# 12-Electrodes.net
KiCad netlist of a schematic drawn in Altium Designer
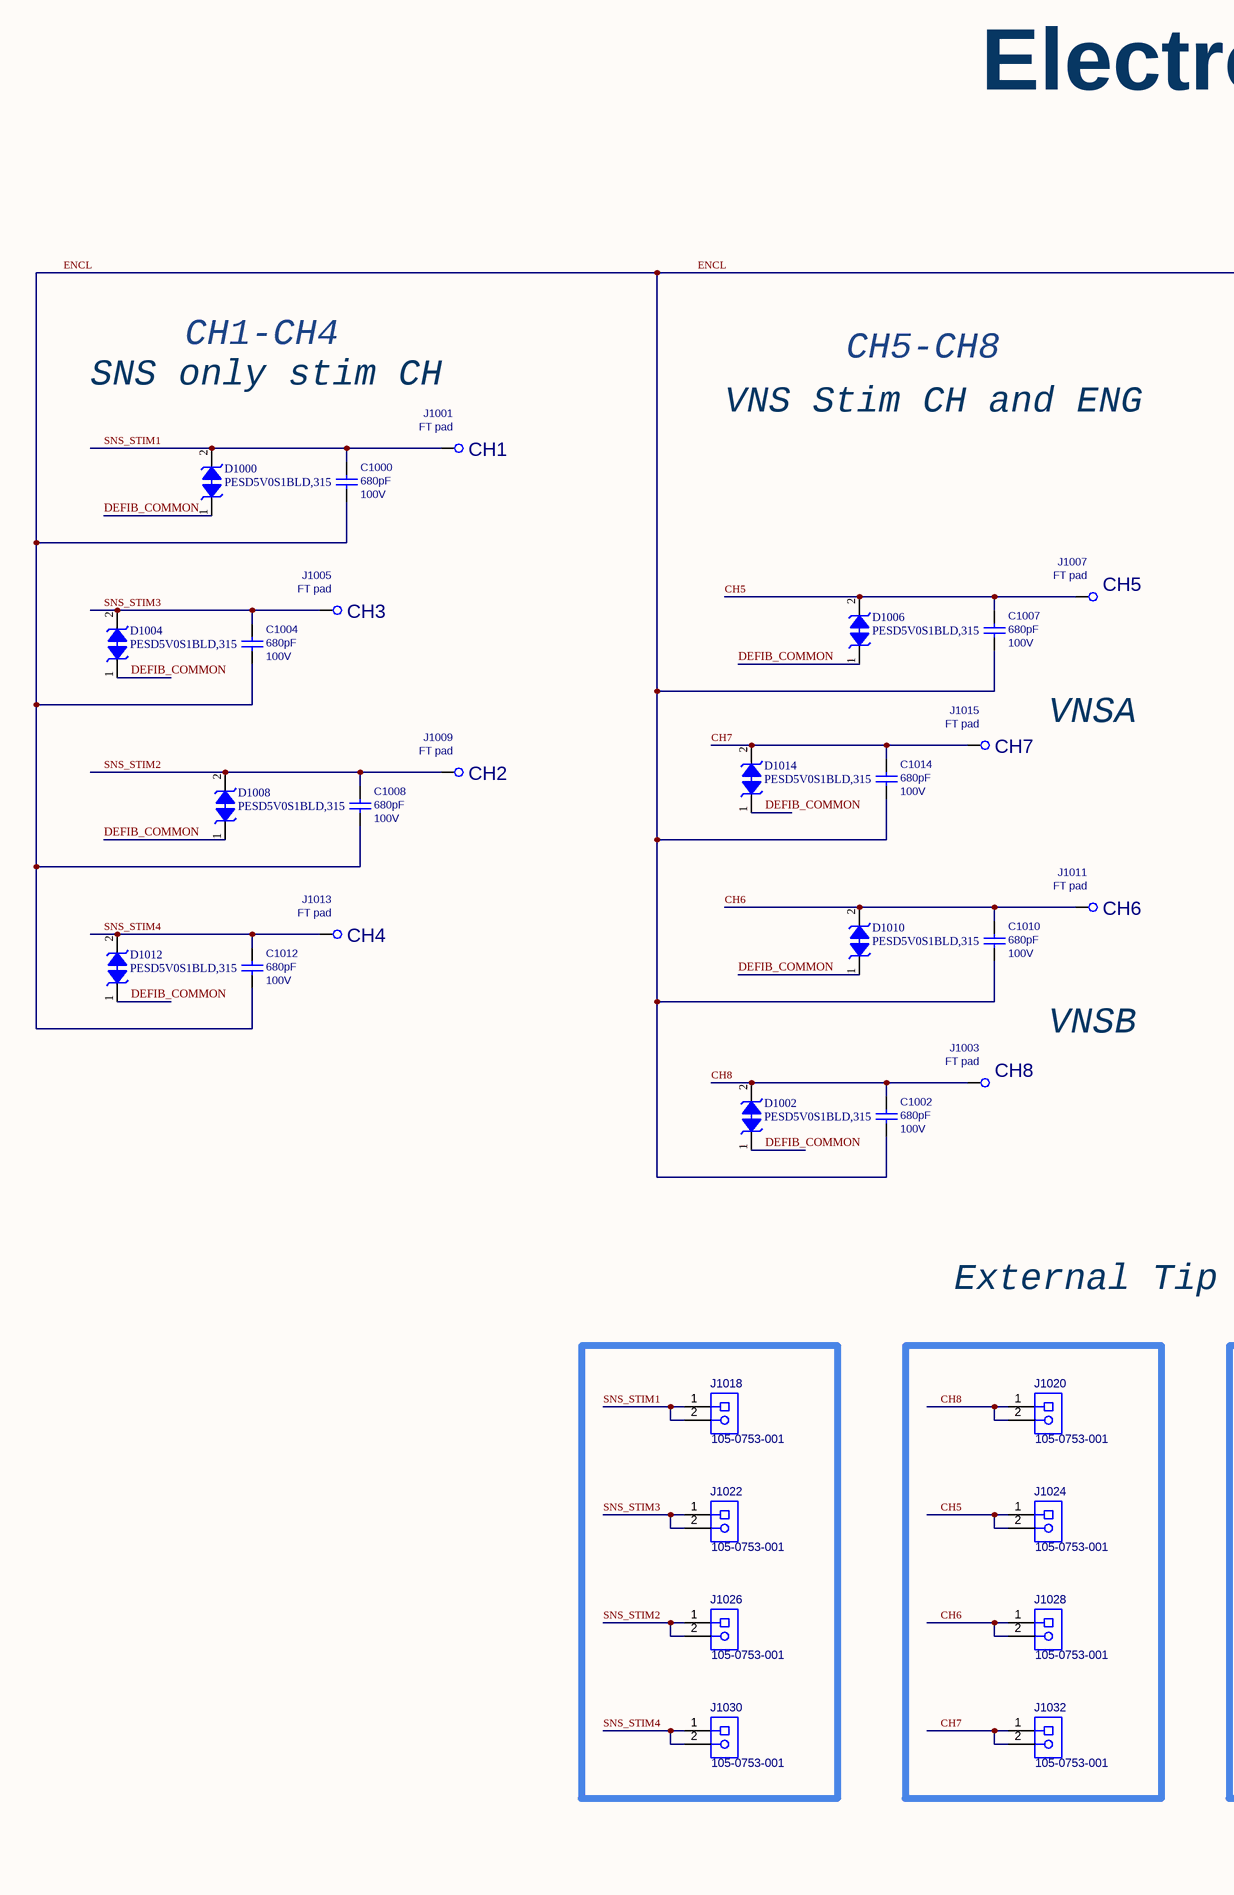
[diagram p0: 12-Electrodes.SchDoc, left]
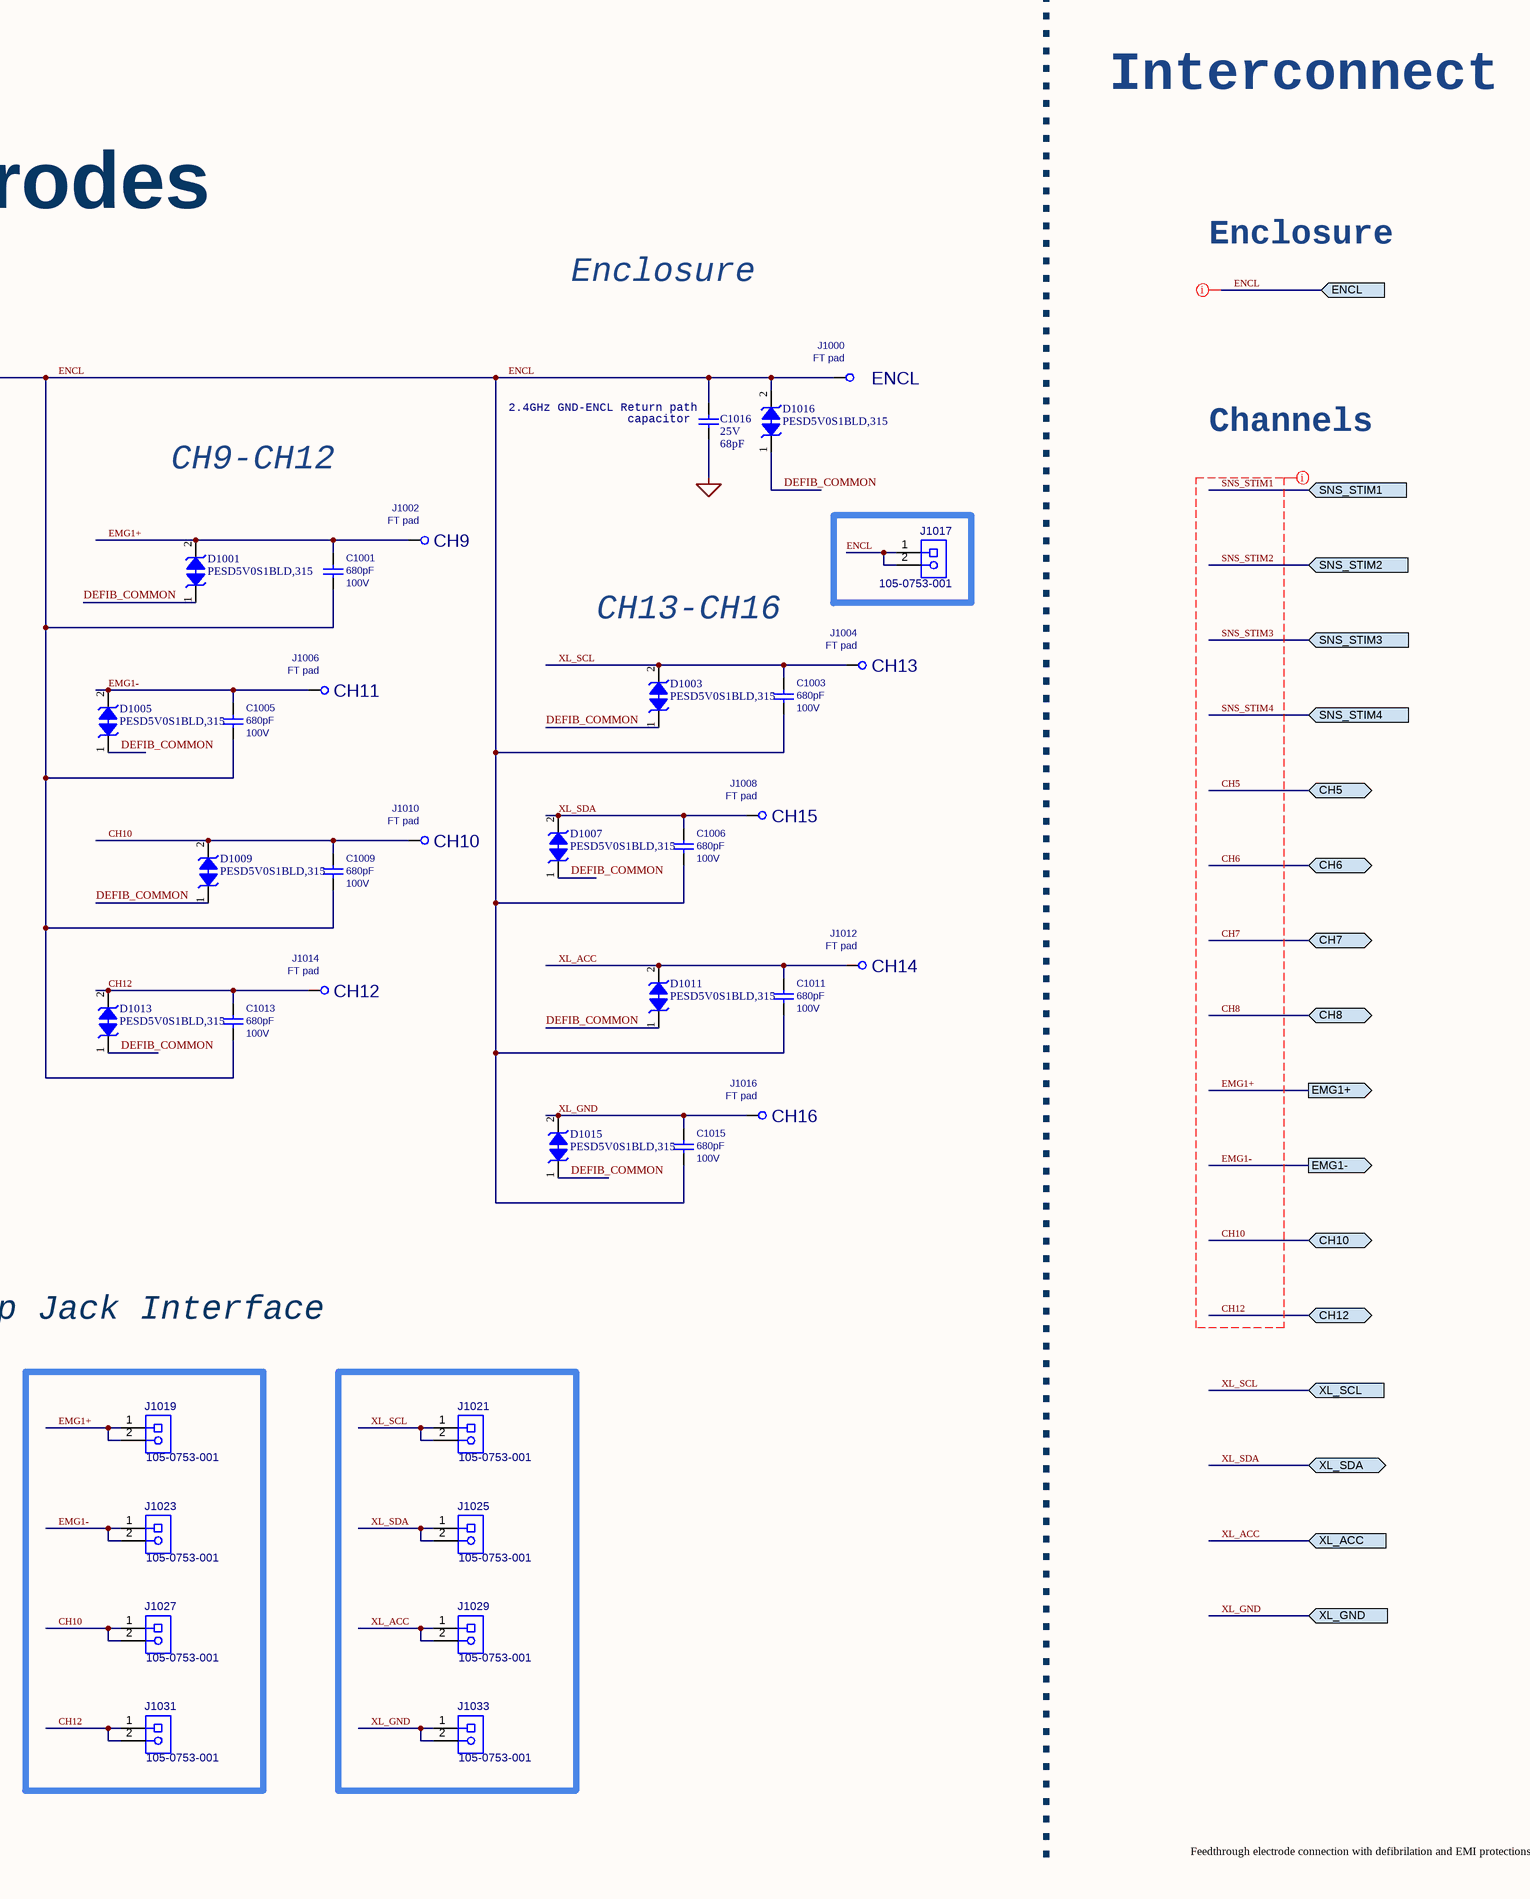
[diagram p1: 12-Electrodes.SchDoc, right]

(export (version "E")
  (design (tool "Eeschema 10.0.6"))
  (components
    (comp (ref "C1000")
      (value "680pF")
      (footprint "CAP0402_REDUCED")
      (description "Capacitor, 680pF, C0G, 100V, 5%, 0402")
      (fields
        (field (name "MANUFACTURER") "TDK")
        (field (name "RATING") "100V")
        (field (name "MANUFACTURER PART NUMBER") "C1005C0G2A681J050BE")
      )
      (libsource (lib "MP-LIBRARY") (part "C1005C0G2A681J050BE"))
    )
    (comp (ref "C1001")
      (value "680pF")
      (footprint "CAP0402_REDUCED")
      (description "Capacitor, 680pF, C0G, 100V, 5%, 0402")
      (fields
        (field (name "MANUFACTURER") "TDK")
        (field (name "RATING") "100V")
        (field (name "MANUFACTURER PART NUMBER") "C1005C0G2A681J050BE")
      )
      (libsource (lib "MP-LIBRARY") (part "C1005C0G2A681J050BE"))
    )
    (comp (ref "C1002")
      (value "680pF")
      (footprint "CAP0402_REDUCED")
      (description "Capacitor, 680pF, C0G, 100V, 5%, 0402")
      (fields
        (field (name "MANUFACTURER") "TDK")
        (field (name "RATING") "100V")
        (field (name "MANUFACTURER PART NUMBER") "C1005C0G2A681J050BE")
      )
      (libsource (lib "MP-LIBRARY") (part "C1005C0G2A681J050BE"))
    )
    (comp (ref "C1003")
      (value "680pF")
      (footprint "CAP0402_REDUCED")
      (description "Capacitor, 680pF, C0G, 100V, 5%, 0402")
      (fields
        (field (name "MANUFACTURER") "TDK")
        (field (name "RATING") "100V")
        (field (name "MANUFACTURER PART NUMBER") "C1005C0G2A681J050BE")
      )
      (libsource (lib "MP-LIBRARY") (part "C1005C0G2A681J050BE"))
    )
    (comp (ref "C1004")
      (value "680pF")
      (footprint "CAP0402_REDUCED")
      (description "Capacitor, 680pF, C0G, 100V, 5%, 0402")
      (fields
        (field (name "MANUFACTURER") "TDK")
        (field (name "RATING") "100V")
        (field (name "MANUFACTURER PART NUMBER") "C1005C0G2A681J050BE")
      )
      (libsource (lib "MP-LIBRARY") (part "C1005C0G2A681J050BE"))
    )
    (comp (ref "C1005")
      (value "680pF")
      (footprint "CAP0402_REDUCED")
      (description "Capacitor, 680pF, C0G, 100V, 5%, 0402")
      (fields
        (field (name "MANUFACTURER") "TDK")
        (field (name "RATING") "100V")
        (field (name "MANUFACTURER PART NUMBER") "C1005C0G2A681J050BE")
      )
      (libsource (lib "MP-LIBRARY") (part "C1005C0G2A681J050BE"))
    )
    (comp (ref "C1006")
      (value "680pF")
      (footprint "CAP0402_REDUCED")
      (description "Capacitor, 680pF, C0G, 100V, 5%, 0402")
      (fields
        (field (name "MANUFACTURER") "TDK")
        (field (name "RATING") "100V")
        (field (name "MANUFACTURER PART NUMBER") "C1005C0G2A681J050BE")
      )
      (libsource (lib "MP-LIBRARY") (part "C1005C0G2A681J050BE"))
    )
    (comp (ref "C1007")
      (value "680pF")
      (footprint "CAP0402_REDUCED")
      (description "Capacitor, 680pF, C0G, 100V, 5%, 0402")
      (fields
        (field (name "MANUFACTURER") "TDK")
        (field (name "RATING") "100V")
        (field (name "MANUFACTURER PART NUMBER") "C1005C0G2A681J050BE")
      )
      (libsource (lib "MP-LIBRARY") (part "C1005C0G2A681J050BE"))
    )
    (comp (ref "C1008")
      (value "680pF")
      (footprint "CAP0402_REDUCED")
      (description "Capacitor, 680pF, C0G, 100V, 5%, 0402")
      (fields
        (field (name "MANUFACTURER") "TDK")
        (field (name "RATING") "100V")
        (field (name "MANUFACTURER PART NUMBER") "C1005C0G2A681J050BE")
      )
      (libsource (lib "MP-LIBRARY") (part "C1005C0G2A681J050BE"))
    )
    (comp (ref "C1009")
      (value "680pF")
      (footprint "CAP0402_REDUCED")
      (description "Capacitor, 680pF, C0G, 100V, 5%, 0402")
      (fields
        (field (name "MANUFACTURER") "TDK")
        (field (name "RATING") "100V")
        (field (name "MANUFACTURER PART NUMBER") "C1005C0G2A681J050BE")
      )
      (libsource (lib "MP-LIBRARY") (part "C1005C0G2A681J050BE"))
    )
    (comp (ref "C1010")
      (value "680pF")
      (footprint "CAP0402_REDUCED")
      (description "Capacitor, 680pF, C0G, 100V, 5%, 0402")
      (fields
        (field (name "MANUFACTURER") "TDK")
        (field (name "RATING") "100V")
        (field (name "MANUFACTURER PART NUMBER") "C1005C0G2A681J050BE")
      )
      (libsource (lib "MP-LIBRARY") (part "C1005C0G2A681J050BE"))
    )
    (comp (ref "C1011")
      (value "680pF")
      (footprint "CAP0402_REDUCED")
      (description "Capacitor, 680pF, C0G, 100V, 5%, 0402")
      (fields
        (field (name "MANUFACTURER") "TDK")
        (field (name "RATING") "100V")
        (field (name "MANUFACTURER PART NUMBER") "C1005C0G2A681J050BE")
      )
      (libsource (lib "MP-LIBRARY") (part "C1005C0G2A681J050BE"))
    )
    (comp (ref "C1012")
      (value "680pF")
      (footprint "CAP0402_REDUCED")
      (description "Capacitor, 680pF, C0G, 100V, 5%, 0402")
      (fields
        (field (name "MANUFACTURER") "TDK")
        (field (name "RATING") "100V")
        (field (name "MANUFACTURER PART NUMBER") "C1005C0G2A681J050BE")
      )
      (libsource (lib "MP-LIBRARY") (part "C1005C0G2A681J050BE"))
    )
    (comp (ref "C1013")
      (value "680pF")
      (footprint "CAP0402_REDUCED")
      (description "Capacitor, 680pF, C0G, 100V, 5%, 0402")
      (fields
        (field (name "MANUFACTURER") "TDK")
        (field (name "RATING") "100V")
        (field (name "MANUFACTURER PART NUMBER") "C1005C0G2A681J050BE")
      )
      (libsource (lib "MP-LIBRARY") (part "C1005C0G2A681J050BE"))
    )
    (comp (ref "C1014")
      (value "680pF")
      (footprint "CAP0402_REDUCED")
      (description "Capacitor, 680pF, C0G, 100V, 5%, 0402")
      (fields
        (field (name "MANUFACTURER") "TDK")
        (field (name "RATING") "100V")
        (field (name "MANUFACTURER PART NUMBER") "C1005C0G2A681J050BE")
      )
      (libsource (lib "MP-LIBRARY") (part "C1005C0G2A681J050BE"))
    )
    (comp (ref "C1015")
      (value "680pF")
      (footprint "CAP0402_REDUCED")
      (description "Capacitor, 680pF, C0G, 100V, 5%, 0402")
      (fields
        (field (name "MANUFACTURER") "TDK")
        (field (name "RATING") "100V")
        (field (name "MANUFACTURER PART NUMBER") "C1005C0G2A681J050BE")
      )
      (libsource (lib "MP-LIBRARY") (part "C1005C0G2A681J050BE"))
    )
    (comp (ref "C1016")
      (value "68pF")
      (footprint "C0201_C")
      (description "Capacitor, 68pF, C0G, 25V, 5%, 0201, Implant-grade")
      (fields
        (field (name "MANUFACTURER") "Murata")
        (field (name "MANUFACTURER PART NUMBER") "GRT0335C1E680JA02D")
        (field (name "VOLTAGE RATING") "25V")
      )
      (libsource (lib "MP-LIBRARY") (part "GRT0335C1E680JA02D"))
    )
    (comp (ref "D1000")
      (value "PESD5V0S1BLD,315")
      (footprint "PESD5V0S1BLD315")
      (description "Diode ESD (Bi-directional)")
      (fields
        (field (name "MOUSER PART NUMBER") "771-PESD5V0S1BLD315")
        (field (name "MANUFACTURER") "Nexperia")
      )
      (libsource (lib "MP-LIBRARY") (part "PESD5V0S1BLD,315"))
    )
    (comp (ref "D1001")
      (value "PESD5V0S1BLD,315")
      (footprint "PESD5V0S1BLD315")
      (description "Diode ESD (Bi-directional)")
      (fields
        (field (name "MOUSER PART NUMBER") "771-PESD5V0S1BLD315")
        (field (name "MANUFACTURER") "Nexperia")
      )
      (libsource (lib "MP-LIBRARY") (part "PESD5V0S1BLD,315"))
    )
    (comp (ref "D1002")
      (value "PESD5V0S1BLD,315")
      (footprint "PESD5V0S1BLD315")
      (description "Diode ESD (Bi-directional)")
      (fields
        (field (name "MOUSER PART NUMBER") "771-PESD5V0S1BLD315")
        (field (name "MANUFACTURER") "Nexperia")
      )
      (libsource (lib "MP-LIBRARY") (part "PESD5V0S1BLD,315"))
    )
    (comp (ref "D1003")
      (value "PESD5V0S1BLD,315")
      (footprint "PESD5V0S1BLD315")
      (description "Diode ESD (Bi-directional)")
      (fields
        (field (name "MOUSER PART NUMBER") "771-PESD5V0S1BLD315")
        (field (name "MANUFACTURER") "Nexperia")
      )
      (libsource (lib "MP-LIBRARY") (part "PESD5V0S1BLD,315"))
    )
    (comp (ref "D1004")
      (value "PESD5V0S1BLD,315")
      (footprint "PESD5V0S1BLD315")
      (description "Diode ESD (Bi-directional)")
      (fields
        (field (name "MOUSER PART NUMBER") "771-PESD5V0S1BLD315")
        (field (name "MANUFACTURER") "Nexperia")
      )
      (libsource (lib "MP-LIBRARY") (part "PESD5V0S1BLD,315"))
    )
    (comp (ref "D1005")
      (value "PESD5V0S1BLD,315")
      (footprint "PESD5V0S1BLD315")
      (description "Diode ESD (Bi-directional)")
      (fields
        (field (name "MOUSER PART NUMBER") "771-PESD5V0S1BLD315")
        (field (name "MANUFACTURER") "Nexperia")
      )
      (libsource (lib "MP-LIBRARY") (part "PESD5V0S1BLD,315"))
    )
    (comp (ref "D1006")
      (value "PESD5V0S1BLD,315")
      (footprint "PESD5V0S1BLD315")
      (description "Diode ESD (Bi-directional)")
      (fields
        (field (name "MOUSER PART NUMBER") "771-PESD5V0S1BLD315")
        (field (name "MANUFACTURER") "Nexperia")
      )
      (libsource (lib "MP-LIBRARY") (part "PESD5V0S1BLD,315"))
    )
    (comp (ref "D1007")
      (value "PESD5V0S1BLD,315")
      (footprint "PESD5V0S1BLD315")
      (description "Diode ESD (Bi-directional)")
      (fields
        (field (name "MOUSER PART NUMBER") "771-PESD5V0S1BLD315")
        (field (name "MANUFACTURER") "Nexperia")
      )
      (libsource (lib "MP-LIBRARY") (part "PESD5V0S1BLD,315"))
    )
    (comp (ref "D1008")
      (value "PESD5V0S1BLD,315")
      (footprint "PESD5V0S1BLD315")
      (description "Diode ESD (Bi-directional)")
      (fields
        (field (name "MOUSER PART NUMBER") "771-PESD5V0S1BLD315")
        (field (name "MANUFACTURER") "Nexperia")
      )
      (libsource (lib "MP-LIBRARY") (part "PESD5V0S1BLD,315"))
    )
    (comp (ref "D1009")
      (value "PESD5V0S1BLD,315")
      (footprint "PESD5V0S1BLD315")
      (description "Diode ESD (Bi-directional)")
      (fields
        (field (name "MOUSER PART NUMBER") "771-PESD5V0S1BLD315")
        (field (name "MANUFACTURER") "Nexperia")
      )
      (libsource (lib "MP-LIBRARY") (part "PESD5V0S1BLD,315"))
    )
    (comp (ref "D1010")
      (value "PESD5V0S1BLD,315")
      (footprint "PESD5V0S1BLD315")
      (description "Diode ESD (Bi-directional)")
      (fields
        (field (name "MOUSER PART NUMBER") "771-PESD5V0S1BLD315")
        (field (name "MANUFACTURER") "Nexperia")
      )
      (libsource (lib "MP-LIBRARY") (part "PESD5V0S1BLD,315"))
    )
    (comp (ref "D1011")
      (value "PESD5V0S1BLD,315")
      (footprint "PESD5V0S1BLD315")
      (description "Diode ESD (Bi-directional)")
      (fields
        (field (name "MOUSER PART NUMBER") "771-PESD5V0S1BLD315")
        (field (name "MANUFACTURER") "Nexperia")
      )
      (libsource (lib "MP-LIBRARY") (part "PESD5V0S1BLD,315"))
    )
    (comp (ref "D1012")
      (value "PESD5V0S1BLD,315")
      (footprint "PESD5V0S1BLD315")
      (description "Diode ESD (Bi-directional)")
      (fields
        (field (name "MOUSER PART NUMBER") "771-PESD5V0S1BLD315")
        (field (name "MANUFACTURER") "Nexperia")
      )
      (libsource (lib "MP-LIBRARY") (part "PESD5V0S1BLD,315"))
    )
    (comp (ref "D1013")
      (value "PESD5V0S1BLD,315")
      (footprint "PESD5V0S1BLD315")
      (description "Diode ESD (Bi-directional)")
      (fields
        (field (name "MOUSER PART NUMBER") "771-PESD5V0S1BLD315")
        (field (name "MANUFACTURER") "Nexperia")
      )
      (libsource (lib "MP-LIBRARY") (part "PESD5V0S1BLD,315"))
    )
    (comp (ref "D1014")
      (value "PESD5V0S1BLD,315")
      (footprint "PESD5V0S1BLD315")
      (description "Diode ESD (Bi-directional)")
      (fields
        (field (name "MOUSER PART NUMBER") "771-PESD5V0S1BLD315")
        (field (name "MANUFACTURER") "Nexperia")
      )
      (libsource (lib "MP-LIBRARY") (part "PESD5V0S1BLD,315"))
    )
    (comp (ref "D1015")
      (value "PESD5V0S1BLD,315")
      (footprint "PESD5V0S1BLD315")
      (description "Diode ESD (Bi-directional)")
      (fields
        (field (name "MOUSER PART NUMBER") "771-PESD5V0S1BLD315")
        (field (name "MANUFACTURER") "Nexperia")
      )
      (libsource (lib "MP-LIBRARY") (part "PESD5V0S1BLD,315"))
    )
    (comp (ref "D1016")
      (value "PESD5V0S1BLD,315")
      (footprint "PESD5V0S1BLD315")
      (description "Diode ESD (Bi-directional)")
      (fields
        (field (name "MOUSER PART NUMBER") "771-PESD5V0S1BLD315")
        (field (name "MANUFACTURER") "Nexperia")
      )
      (libsource (lib "MP-LIBRARY") (part "PESD5V0S1BLD,315"))
    )
    (comp (ref "J1000")
      (value "FT pad")
      (footprint "FEEDHOLE_20mil")
      (description "FT pad, Thru-hole, 20 mil hole")
      (fields (field (name "Comment") "THPAD_20m"))
      (libsource (lib "MP-LIBRARY") (part "HOLE_20m"))
    )
    (comp (ref "J1001")
      (value "FT pad")
      (footprint "FEEDHOLE_20mil")
      (description "FT pad, Thru-hole, 20 mil hole")
      (fields (field (name "Comment") "THPAD_20m"))
      (libsource (lib "MP-LIBRARY") (part "HOLE_20m"))
    )
    (comp (ref "J1002")
      (value "FT pad")
      (footprint "FEEDHOLE_20mil")
      (description "FT pad, Thru-hole, 20 mil hole")
      (fields (field (name "Comment") "THPAD_20m"))
      (libsource (lib "MP-LIBRARY") (part "HOLE_20m"))
    )
    (comp (ref "J1003")
      (value "FT pad")
      (footprint "FEEDHOLE_20mil")
      (description "FT pad, Thru-hole, 20 mil hole")
      (fields (field (name "Comment") "THPAD_20m"))
      (libsource (lib "MP-LIBRARY") (part "HOLE_20m"))
    )
    (comp (ref "J1004")
      (value "FT pad")
      (footprint "FEEDHOLE_20mil")
      (description "FT pad, Thru-hole, 20 mil hole")
      (fields (field (name "Comment") "THPAD_20m"))
      (libsource (lib "MP-LIBRARY") (part "HOLE_20m"))
    )
    (comp (ref "J1005")
      (value "FT pad")
      (footprint "FEEDHOLE_20mil")
      (description "FT pad, Thru-hole, 20 mil hole")
      (fields (field (name "Comment") "THPAD_20m"))
      (libsource (lib "MP-LIBRARY") (part "HOLE_20m"))
    )
    (comp (ref "J1006")
      (value "FT pad")
      (footprint "FEEDHOLE_20mil")
      (description "FT pad, Thru-hole, 20 mil hole")
      (fields (field (name "Comment") "THPAD_20m"))
      (libsource (lib "MP-LIBRARY") (part "HOLE_20m"))
    )
    (comp (ref "J1007")
      (value "FT pad")
      (footprint "FEEDHOLE_20mil")
      (description "FT pad, Thru-hole, 20 mil hole")
      (fields (field (name "Comment") "THPAD_20m"))
      (libsource (lib "MP-LIBRARY") (part "HOLE_20m"))
    )
    (comp (ref "J1008")
      (value "FT pad")
      (footprint "FEEDHOLE_20mil")
      (description "FT pad, Thru-hole, 20 mil hole")
      (fields (field (name "Comment") "THPAD_20m"))
      (libsource (lib "MP-LIBRARY") (part "HOLE_20m"))
    )
    (comp (ref "J1009")
      (value "FT pad")
      (footprint "FEEDHOLE_20mil")
      (description "FT pad, Thru-hole, 20 mil hole")
      (fields (field (name "Comment") "THPAD_20m"))
      (libsource (lib "MP-LIBRARY") (part "HOLE_20m"))
    )
    (comp (ref "J1010")
      (value "FT pad")
      (footprint "FEEDHOLE_20mil")
      (description "FT pad, Thru-hole, 20 mil hole")
      (fields (field (name "Comment") "THPAD_20m"))
      (libsource (lib "MP-LIBRARY") (part "HOLE_20m"))
    )
    (comp (ref "J1011")
      (value "FT pad")
      (footprint "FEEDHOLE_20mil")
      (description "FT pad, Thru-hole, 20 mil hole")
      (fields (field (name "Comment") "THPAD_20m"))
      (libsource (lib "MP-LIBRARY") (part "HOLE_20m"))
    )
    (comp (ref "J1012")
      (value "FT pad")
      (footprint "FEEDHOLE_20mil")
      (description "FT pad, Thru-hole, 20 mil hole")
      (fields (field (name "Comment") "THPAD_20m"))
      (libsource (lib "MP-LIBRARY") (part "HOLE_20m"))
    )
    (comp (ref "J1013")
      (value "FT pad")
      (footprint "FEEDHOLE_20mil")
      (description "FT pad, Thru-hole, 20 mil hole")
      (fields (field (name "Comment") "THPAD_20m"))
      (libsource (lib "MP-LIBRARY") (part "HOLE_20m"))
    )
    (comp (ref "J1014")
      (value "FT pad")
      (footprint "FEEDHOLE_20mil")
      (description "FT pad, Thru-hole, 20 mil hole")
      (fields (field (name "Comment") "THPAD_20m"))
      (libsource (lib "MP-LIBRARY") (part "HOLE_20m"))
    )
    (comp (ref "J1015")
      (value "FT pad")
      (footprint "FEEDHOLE_20mil")
      (description "FT pad, Thru-hole, 20 mil hole")
      (fields (field (name "Comment") "THPAD_20m"))
      (libsource (lib "MP-LIBRARY") (part "HOLE_20m"))
    )
    (comp (ref "J1016")
      (value "FT pad")
      (footprint "FEEDHOLE_20mil")
      (description "FT pad, Thru-hole, 20 mil hole")
      (fields (field (name "Comment") "THPAD_20m"))
      (libsource (lib "MP-LIBRARY") (part "HOLE_20m"))
    )
    (comp (ref "J1017")
      (value "105-0753-001")
      (footprint "105-07XX-001")
      (description "Connector, Bannana Tip, Through Hole, Rodent Study lead connector")
      (fields
        (field (name "MANUFACTURER") "Cinch Connectivity Solutions Johnson")
        (field (name "Comment") "105-07XX-001")
      )
      (libsource (lib "MP-LIBRARY") (part "105-07XX-001"))
    )
    (comp (ref "J1018")
      (value "105-0753-001")
      (footprint "105-07XX-001")
      (description "Connector, Bannana Tip, Through Hole, Rodent Study lead connector")
      (fields
        (field (name "MANUFACTURER") "Cinch Connectivity Solutions Johnson")
        (field (name "Comment") "105-07XX-001")
      )
      (libsource (lib "MP-LIBRARY") (part "105-07XX-001"))
    )
    (comp (ref "J1019")
      (value "105-0753-001")
      (footprint "105-07XX-001")
      (description "Connector, Bannana Tip, Through Hole, Rodent Study lead connector")
      (fields
        (field (name "MANUFACTURER") "Cinch Connectivity Solutions Johnson")
        (field (name "Comment") "105-07XX-001")
      )
      (libsource (lib "MP-LIBRARY") (part "105-07XX-001"))
    )
    (comp (ref "J1020")
      (value "105-0753-001")
      (footprint "105-07XX-001")
      (description "Connector, Bannana Tip, Through Hole, Rodent Study lead connector")
      (fields
        (field (name "MANUFACTURER") "Cinch Connectivity Solutions Johnson")
        (field (name "Comment") "105-07XX-001")
      )
      (libsource (lib "MP-LIBRARY") (part "105-07XX-001"))
    )
    (comp (ref "J1021")
      (value "105-0753-001")
      (footprint "105-07XX-001")
      (description "Connector, Bannana Tip, Through Hole, Rodent Study lead connector")
      (fields
        (field (name "MANUFACTURER") "Cinch Connectivity Solutions Johnson")
        (field (name "Comment") "105-07XX-001")
      )
      (libsource (lib "MP-LIBRARY") (part "105-07XX-001"))
    )
    (comp (ref "J1022")
      (value "105-0753-001")
      (footprint "105-07XX-001")
      (description "Connector, Bannana Tip, Through Hole, Rodent Study lead connector")
      (fields
        (field (name "MANUFACTURER") "Cinch Connectivity Solutions Johnson")
        (field (name "Comment") "105-07XX-001")
      )
      (libsource (lib "MP-LIBRARY") (part "105-07XX-001"))
    )
    (comp (ref "J1023")
      (value "105-0753-001")
      (footprint "105-07XX-001")
      (description "Connector, Bannana Tip, Through Hole, Rodent Study lead connector")
      (fields
        (field (name "MANUFACTURER") "Cinch Connectivity Solutions Johnson")
        (field (name "Comment") "105-07XX-001")
      )
      (libsource (lib "MP-LIBRARY") (part "105-07XX-001"))
    )
    (comp (ref "J1024")
      (value "105-0753-001")
      (footprint "105-07XX-001")
      (description "Connector, Bannana Tip, Through Hole, Rodent Study lead connector")
      (fields
        (field (name "MANUFACTURER") "Cinch Connectivity Solutions Johnson")
        (field (name "Comment") "105-07XX-001")
      )
      (libsource (lib "MP-LIBRARY") (part "105-07XX-001"))
    )
    (comp (ref "J1025")
      (value "105-0753-001")
      (footprint "105-07XX-001")
      (description "Connector, Bannana Tip, Through Hole, Rodent Study lead connector")
      (fields
        (field (name "MANUFACTURER") "Cinch Connectivity Solutions Johnson")
        (field (name "Comment") "105-07XX-001")
      )
      (libsource (lib "MP-LIBRARY") (part "105-07XX-001"))
    )
    (comp (ref "J1026")
      (value "105-0753-001")
      (footprint "105-07XX-001")
      (description "Connector, Bannana Tip, Through Hole, Rodent Study lead connector")
      (fields
        (field (name "MANUFACTURER") "Cinch Connectivity Solutions Johnson")
        (field (name "Comment") "105-07XX-001")
      )
      (libsource (lib "MP-LIBRARY") (part "105-07XX-001"))
    )
    (comp (ref "J1027")
      (value "105-0753-001")
      (footprint "105-07XX-001")
      (description "Connector, Bannana Tip, Through Hole, Rodent Study lead connector")
      (fields
        (field (name "MANUFACTURER") "Cinch Connectivity Solutions Johnson")
        (field (name "Comment") "105-07XX-001")
      )
      (libsource (lib "MP-LIBRARY") (part "105-07XX-001"))
    )
    (comp (ref "J1028")
      (value "105-0753-001")
      (footprint "105-07XX-001")
      (description "Connector, Bannana Tip, Through Hole, Rodent Study lead connector")
      (fields
        (field (name "MANUFACTURER") "Cinch Connectivity Solutions Johnson")
        (field (name "Comment") "105-07XX-001")
      )
      (libsource (lib "MP-LIBRARY") (part "105-07XX-001"))
    )
    (comp (ref "J1029")
      (value "105-0753-001")
      (footprint "105-07XX-001")
      (description "Connector, Bannana Tip, Through Hole, Rodent Study lead connector")
      (fields
        (field (name "MANUFACTURER") "Cinch Connectivity Solutions Johnson")
        (field (name "Comment") "105-07XX-001")
      )
      (libsource (lib "MP-LIBRARY") (part "105-07XX-001"))
    )
    (comp (ref "J1030")
      (value "105-0753-001")
      (footprint "105-07XX-001")
      (description "Connector, Bannana Tip, Through Hole, Rodent Study lead connector")
      (fields
        (field (name "MANUFACTURER") "Cinch Connectivity Solutions Johnson")
        (field (name "Comment") "105-07XX-001")
      )
      (libsource (lib "MP-LIBRARY") (part "105-07XX-001"))
    )
    (comp (ref "J1031")
      (value "105-0753-001")
      (footprint "105-07XX-001")
      (description "Connector, Bannana Tip, Through Hole, Rodent Study lead connector")
      (fields
        (field (name "MANUFACTURER") "Cinch Connectivity Solutions Johnson")
        (field (name "Comment") "105-07XX-001")
      )
      (libsource (lib "MP-LIBRARY") (part "105-07XX-001"))
    )
    (comp (ref "J1032")
      (value "105-0753-001")
      (footprint "105-07XX-001")
      (description "Connector, Bannana Tip, Through Hole, Rodent Study lead connector")
      (fields
        (field (name "MANUFACTURER") "Cinch Connectivity Solutions Johnson")
        (field (name "Comment") "105-07XX-001")
      )
      (libsource (lib "MP-LIBRARY") (part "105-07XX-001"))
    )
    (comp (ref "J1033")
      (value "105-0753-001")
      (footprint "105-07XX-001")
      (description "Connector, Bannana Tip, Through Hole, Rodent Study lead connector")
      (fields
        (field (name "MANUFACTURER") "Cinch Connectivity Solutions Johnson")
        (field (name "Comment") "105-07XX-001")
      )
      (libsource (lib "MP-LIBRARY") (part "105-07XX-001"))
    )
  )
  (nets
    (net (code "1") (name "/CH5") (class "Default")
      (node (ref "C1007") (pin "2") (pinfunction "2_2") (pintype "passive"))
      (node (ref "D1006") (pin "2") (pinfunction "K2_2") (pintype "passive"))
      (node (ref "J1007") (pin "1") (pinfunction "1_1") (pintype "passive"))
      (node (ref "J1024") (pin "1") (pinfunction "1_1") (pintype "passive"))
      (node (ref "J1024") (pin "2") (pinfunction "2_2") (pintype "passive"))
    )
    (net (code "2") (name "/CH6") (class "Default")
      (node (ref "C1010") (pin "2") (pinfunction "2_2") (pintype "passive"))
      (node (ref "D1010") (pin "2") (pinfunction "K2_2") (pintype "passive"))
      (node (ref "J1011") (pin "1") (pinfunction "1_1") (pintype "passive"))
      (node (ref "J1028") (pin "1") (pinfunction "1_1") (pintype "passive"))
      (node (ref "J1028") (pin "2") (pinfunction "2_2") (pintype "passive"))
    )
    (net (code "3") (name "/CH7") (class "Default")
      (node (ref "C1014") (pin "2") (pinfunction "2_2") (pintype "passive"))
      (node (ref "D1014") (pin "2") (pinfunction "K2_2") (pintype "passive"))
      (node (ref "J1015") (pin "1") (pinfunction "1_1") (pintype "passive"))
      (node (ref "J1032") (pin "1") (pinfunction "1_1") (pintype "passive"))
      (node (ref "J1032") (pin "2") (pinfunction "2_2") (pintype "passive"))
    )
    (net (code "4") (name "/CH8") (class "Default")
      (node (ref "C1002") (pin "2") (pinfunction "2_2") (pintype "passive"))
      (node (ref "D1002") (pin "2") (pinfunction "K2_2") (pintype "passive"))
      (node (ref "J1003") (pin "1") (pinfunction "1_1") (pintype "passive"))
      (node (ref "J1020") (pin "1") (pinfunction "1_1") (pintype "passive"))
      (node (ref "J1020") (pin "2") (pinfunction "2_2") (pintype "passive"))
    )
    (net (code "5") (name "/CH10") (class "Default")
      (node (ref "C1009") (pin "2") (pinfunction "2_2") (pintype "passive"))
      (node (ref "D1009") (pin "2") (pinfunction "K2_2") (pintype "passive"))
      (node (ref "J1010") (pin "1") (pinfunction "1_1") (pintype "passive"))
      (node (ref "J1027") (pin "1") (pinfunction "1_1") (pintype "passive"))
      (node (ref "J1027") (pin "2") (pinfunction "2_2") (pintype "passive"))
    )
    (net (code "6") (name "/CH12") (class "Default")
      (node (ref "C1013") (pin "2") (pinfunction "2_2") (pintype "passive"))
      (node (ref "D1013") (pin "2") (pinfunction "K2_2") (pintype "passive"))
      (node (ref "J1014") (pin "1") (pinfunction "1_1") (pintype "passive"))
      (node (ref "J1031") (pin "1") (pinfunction "1_1") (pintype "passive"))
      (node (ref "J1031") (pin "2") (pinfunction "2_2") (pintype "passive"))
    )
    (net (code "7") (name "/DEFIB_COMMON") (class "Default")
      (node (ref "D1000") (pin "1") (pinfunction "K1_1") (pintype "passive"))
      (node (ref "D1001") (pin "1") (pinfunction "K1_1") (pintype "passive"))
      (node (ref "D1002") (pin "1") (pinfunction "K1_1") (pintype "passive"))
      (node (ref "D1003") (pin "1") (pinfunction "K1_1") (pintype "passive"))
      (node (ref "D1004") (pin "1") (pinfunction "K1_1") (pintype "passive"))
      (node (ref "D1005") (pin "1") (pinfunction "K1_1") (pintype "passive"))
      (node (ref "D1006") (pin "1") (pinfunction "K1_1") (pintype "passive"))
      (node (ref "D1007") (pin "1") (pinfunction "K1_1") (pintype "passive"))
      (node (ref "D1008") (pin "1") (pinfunction "K1_1") (pintype "passive"))
      (node (ref "D1009") (pin "1") (pinfunction "K1_1") (pintype "passive"))
      (node (ref "D1010") (pin "1") (pinfunction "K1_1") (pintype "passive"))
      (node (ref "D1011") (pin "1") (pinfunction "K1_1") (pintype "passive"))
      (node (ref "D1012") (pin "1") (pinfunction "K1_1") (pintype "passive"))
      (node (ref "D1013") (pin "1") (pinfunction "K1_1") (pintype "passive"))
      (node (ref "D1014") (pin "1") (pinfunction "K1_1") (pintype "passive"))
      (node (ref "D1015") (pin "1") (pinfunction "K1_1") (pintype "passive"))
      (node (ref "D1016") (pin "1") (pinfunction "K1_1") (pintype "passive"))
    )
    (net (code "8") (name "/EMG1+") (class "Default")
      (node (ref "C1001") (pin "2") (pinfunction "2_2") (pintype "passive"))
      (node (ref "D1001") (pin "2") (pinfunction "K2_2") (pintype "passive"))
      (node (ref "J1002") (pin "1") (pinfunction "1_1") (pintype "passive"))
      (node (ref "J1019") (pin "1") (pinfunction "1_1") (pintype "passive"))
      (node (ref "J1019") (pin "2") (pinfunction "2_2") (pintype "passive"))
    )
    (net (code "9") (name "/EMG1-") (class "Default")
      (node (ref "C1005") (pin "2") (pinfunction "2_2") (pintype "passive"))
      (node (ref "D1005") (pin "2") (pinfunction "K2_2") (pintype "passive"))
      (node (ref "J1006") (pin "1") (pinfunction "1_1") (pintype "passive"))
      (node (ref "J1023") (pin "1") (pinfunction "1_1") (pintype "passive"))
      (node (ref "J1023") (pin "2") (pinfunction "2_2") (pintype "passive"))
    )
    (net (code "10") (name "/ENCL") (class "Default")
      (node (ref "C1000") (pin "1") (pinfunction "1_1") (pintype "passive"))
      (node (ref "C1001") (pin "1") (pinfunction "1_1") (pintype "passive"))
      (node (ref "C1002") (pin "1") (pinfunction "1_1") (pintype "passive"))
      (node (ref "C1003") (pin "1") (pinfunction "1_1") (pintype "passive"))
      (node (ref "C1004") (pin "1") (pinfunction "1_1") (pintype "passive"))
      (node (ref "C1005") (pin "1") (pinfunction "1_1") (pintype "passive"))
      (node (ref "C1006") (pin "1") (pinfunction "1_1") (pintype "passive"))
      (node (ref "C1007") (pin "1") (pinfunction "1_1") (pintype "passive"))
      (node (ref "C1008") (pin "1") (pinfunction "1_1") (pintype "passive"))
      (node (ref "C1009") (pin "1") (pinfunction "1_1") (pintype "passive"))
      (node (ref "C1010") (pin "1") (pinfunction "1_1") (pintype "passive"))
      (node (ref "C1011") (pin "1") (pinfunction "1_1") (pintype "passive"))
      (node (ref "C1012") (pin "1") (pinfunction "1_1") (pintype "passive"))
      (node (ref "C1013") (pin "1") (pinfunction "1_1") (pintype "passive"))
      (node (ref "C1014") (pin "1") (pinfunction "1_1") (pintype "passive"))
      (node (ref "C1015") (pin "1") (pinfunction "1_1") (pintype "passive"))
      (node (ref "C1016") (pin "2") (pinfunction "2_2") (pintype "passive"))
      (node (ref "D1016") (pin "2") (pinfunction "K2_2") (pintype "passive"))
      (node (ref "J1000") (pin "1") (pinfunction "1_1") (pintype "passive"))
      (node (ref "J1017") (pin "1") (pinfunction "1_1") (pintype "passive"))
      (node (ref "J1017") (pin "2") (pinfunction "2_2") (pintype "passive"))
    )
    (net (code "11") (name "/SNS_STIM1") (class "Default")
      (node (ref "C1000") (pin "2") (pinfunction "2_2") (pintype "passive"))
      (node (ref "D1000") (pin "2") (pinfunction "K2_2") (pintype "passive"))
      (node (ref "J1001") (pin "1") (pinfunction "1_1") (pintype "passive"))
      (node (ref "J1018") (pin "1") (pinfunction "1_1") (pintype "passive"))
      (node (ref "J1018") (pin "2") (pinfunction "2_2") (pintype "passive"))
    )
    (net (code "12") (name "/SNS_STIM2") (class "Default")
      (node (ref "C1008") (pin "2") (pinfunction "2_2") (pintype "passive"))
      (node (ref "D1008") (pin "2") (pinfunction "K2_2") (pintype "passive"))
      (node (ref "J1009") (pin "1") (pinfunction "1_1") (pintype "passive"))
      (node (ref "J1026") (pin "1") (pinfunction "1_1") (pintype "passive"))
      (node (ref "J1026") (pin "2") (pinfunction "2_2") (pintype "passive"))
    )
    (net (code "13") (name "/SNS_STIM3") (class "Default")
      (node (ref "C1004") (pin "2") (pinfunction "2_2") (pintype "passive"))
      (node (ref "D1004") (pin "2") (pinfunction "K2_2") (pintype "passive"))
      (node (ref "J1005") (pin "1") (pinfunction "1_1") (pintype "passive"))
      (node (ref "J1022") (pin "1") (pinfunction "1_1") (pintype "passive"))
      (node (ref "J1022") (pin "2") (pinfunction "2_2") (pintype "passive"))
    )
    (net (code "14") (name "/SNS_STIM4") (class "Default")
      (node (ref "C1012") (pin "2") (pinfunction "2_2") (pintype "passive"))
      (node (ref "D1012") (pin "2") (pinfunction "K2_2") (pintype "passive"))
      (node (ref "J1013") (pin "1") (pinfunction "1_1") (pintype "passive"))
      (node (ref "J1030") (pin "1") (pinfunction "1_1") (pintype "passive"))
      (node (ref "J1030") (pin "2") (pinfunction "2_2") (pintype "passive"))
    )
    (net (code "15") (name "/XL_ACC") (class "Default")
      (node (ref "C1011") (pin "2") (pinfunction "2_2") (pintype "passive"))
      (node (ref "D1011") (pin "2") (pinfunction "K2_2") (pintype "passive"))
      (node (ref "J1012") (pin "1") (pinfunction "1_1") (pintype "passive"))
      (node (ref "J1029") (pin "1") (pinfunction "1_1") (pintype "passive"))
      (node (ref "J1029") (pin "2") (pinfunction "2_2") (pintype "passive"))
    )
    (net (code "16") (name "/XL_GND") (class "Default")
      (node (ref "C1015") (pin "2") (pinfunction "2_2") (pintype "passive"))
      (node (ref "D1015") (pin "2") (pinfunction "K2_2") (pintype "passive"))
      (node (ref "J1016") (pin "1") (pinfunction "1_1") (pintype "passive"))
      (node (ref "J1033") (pin "1") (pinfunction "1_1") (pintype "passive"))
      (node (ref "J1033") (pin "2") (pinfunction "2_2") (pintype "passive"))
    )
    (net (code "17") (name "/XL_SCL") (class "Default")
      (node (ref "C1003") (pin "2") (pinfunction "2_2") (pintype "passive"))
      (node (ref "D1003") (pin "2") (pinfunction "K2_2") (pintype "passive"))
      (node (ref "J1004") (pin "1") (pinfunction "1_1") (pintype "passive"))
      (node (ref "J1021") (pin "1") (pinfunction "1_1") (pintype "passive"))
      (node (ref "J1021") (pin "2") (pinfunction "2_2") (pintype "passive"))
    )
    (net (code "18") (name "/XL_SDA") (class "Default")
      (node (ref "C1006") (pin "2") (pinfunction "2_2") (pintype "passive"))
      (node (ref "D1007") (pin "2") (pinfunction "K2_2") (pintype "passive"))
      (node (ref "J1008") (pin "1") (pinfunction "1_1") (pintype "passive"))
      (node (ref "J1025") (pin "1") (pinfunction "1_1") (pintype "passive"))
      (node (ref "J1025") (pin "2") (pinfunction "2_2") (pintype "passive"))
    )
    (net (code "19") (name "GND") (class "Default")
      (node (ref "C1016") (pin "1") (pinfunction "1_1") (pintype "passive"))
    )
  )
)
